# Line_Sensor.net
KiCad netlist of a schematic drawn in EAGLE
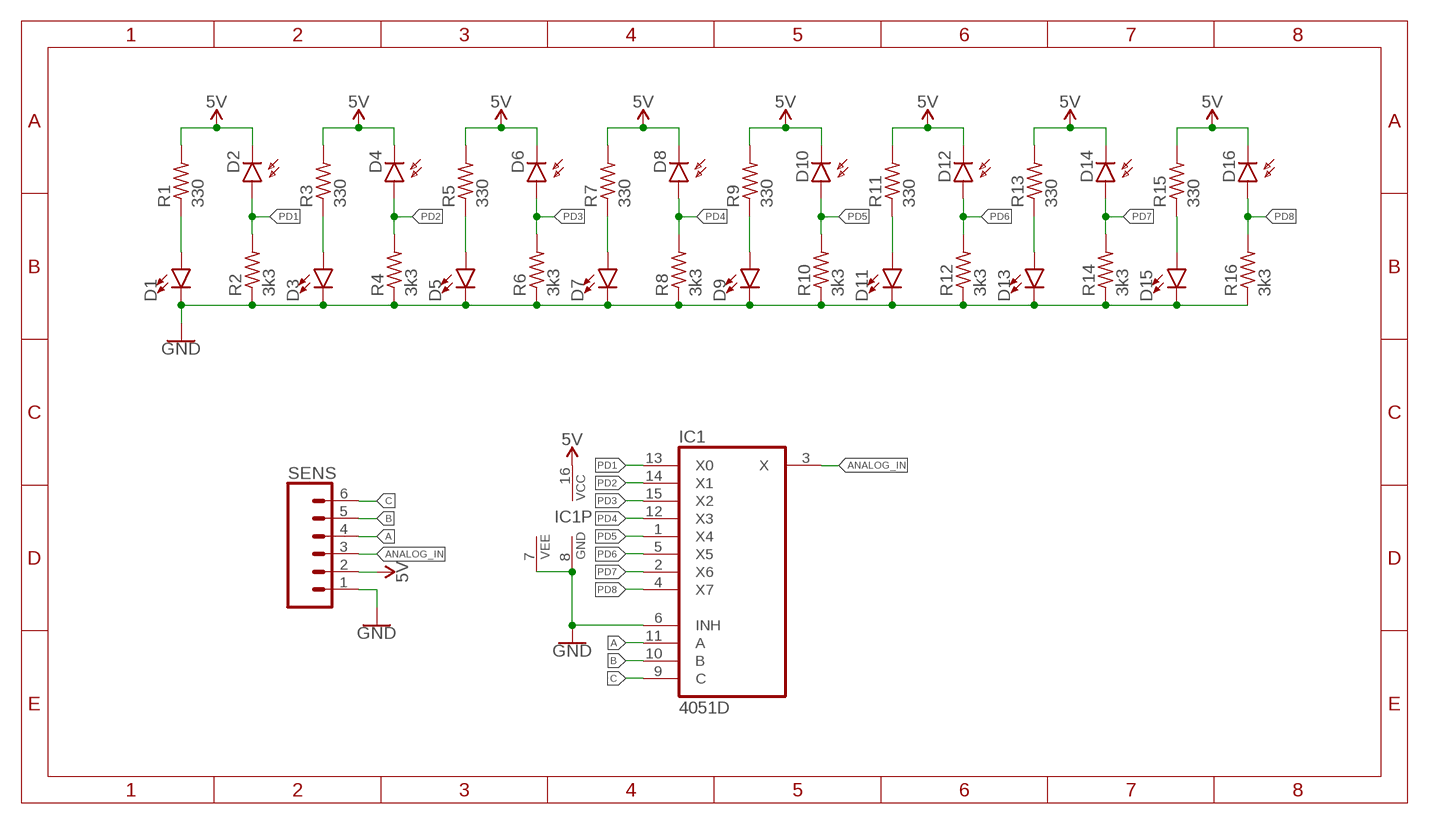
[diagram p0: schematic, sheet 1]

(export (version "E")
  (design (tool "Eeschema 10.0.6"))
  (components
    (comp (ref "D1")
      (value "LED3MM")
      (footprint "eagle-import:LED_3MM")
      (libsource (lib "eagle-import") (part "LED3MM"))
    )
    (comp (ref "D2")
      (value "SFH225")
      (footprint "eagle-import:SFH225")
      (libsource (lib "eagle-import") (part "SFH225"))
    )
    (comp (ref "D3")
      (value "LED3MM")
      (footprint "eagle-import:LED_3MM")
      (libsource (lib "eagle-import") (part "LED3MM"))
    )
    (comp (ref "D4")
      (value "SFH225")
      (footprint "eagle-import:SFH225")
      (libsource (lib "eagle-import") (part "SFH225"))
    )
    (comp (ref "D5")
      (value "LED3MM")
      (footprint "eagle-import:LED_3MM")
      (libsource (lib "eagle-import") (part "LED3MM"))
    )
    (comp (ref "D6")
      (value "SFH225")
      (footprint "eagle-import:SFH225")
      (libsource (lib "eagle-import") (part "SFH225"))
    )
    (comp (ref "D7")
      (value "LED3MM")
      (footprint "eagle-import:LED_3MM")
      (libsource (lib "eagle-import") (part "LED3MM"))
    )
    (comp (ref "D8")
      (value "SFH225")
      (footprint "eagle-import:SFH225")
      (libsource (lib "eagle-import") (part "SFH225"))
    )
    (comp (ref "D9")
      (value "LED3MM")
      (footprint "eagle-import:LED_3MM")
      (libsource (lib "eagle-import") (part "LED3MM"))
    )
    (comp (ref "D10")
      (value "SFH225")
      (footprint "eagle-import:SFH225")
      (libsource (lib "eagle-import") (part "SFH225"))
    )
    (comp (ref "D11")
      (value "LED3MM")
      (footprint "eagle-import:LED_3MM")
      (libsource (lib "eagle-import") (part "LED3MM"))
    )
    (comp (ref "D12")
      (value "SFH225")
      (footprint "eagle-import:SFH225")
      (libsource (lib "eagle-import") (part "SFH225"))
    )
    (comp (ref "D13")
      (value "LED3MM")
      (footprint "eagle-import:LED_3MM")
      (libsource (lib "eagle-import") (part "LED3MM"))
    )
    (comp (ref "D14")
      (value "SFH225")
      (footprint "eagle-import:SFH225")
      (libsource (lib "eagle-import") (part "SFH225"))
    )
    (comp (ref "D15")
      (value "LED3MM")
      (footprint "eagle-import:LED_3MM")
      (libsource (lib "eagle-import") (part "LED3MM"))
    )
    (comp (ref "D16")
      (value "SFH225")
      (footprint "eagle-import:SFH225")
      (libsource (lib "eagle-import") (part "SFH225"))
    )
    (comp (ref "IC1")
      (value "4051D")
      (footprint "eagle-import:SO16")
      (libsource (lib "eagle-import") (part "4051D"))
    )
    (comp (ref "R1")
      (value "330")
      (footprint "eagle-import:0207_9")
      (libsource (lib "eagle-import") (part "R-US_0207/9"))
    )
    (comp (ref "R2")
      (value "3k3")
      (footprint "eagle-import:0207_9")
      (libsource (lib "eagle-import") (part "R-US_0207/9"))
    )
    (comp (ref "R3")
      (value "330")
      (footprint "eagle-import:0207_9")
      (libsource (lib "eagle-import") (part "R-US_0207/9"))
    )
    (comp (ref "R4")
      (value "3k3")
      (footprint "eagle-import:0207_9")
      (libsource (lib "eagle-import") (part "R-US_0207/9"))
    )
    (comp (ref "R5")
      (value "330")
      (footprint "eagle-import:0207_9")
      (libsource (lib "eagle-import") (part "R-US_0207/9"))
    )
    (comp (ref "R6")
      (value "3k3")
      (footprint "eagle-import:0207_9")
      (libsource (lib "eagle-import") (part "R-US_0207/9"))
    )
    (comp (ref "R7")
      (value "330")
      (footprint "eagle-import:0207_9")
      (libsource (lib "eagle-import") (part "R-US_0207/9"))
    )
    (comp (ref "R8")
      (value "3k3")
      (footprint "eagle-import:0207_9")
      (libsource (lib "eagle-import") (part "R-US_0207/9"))
    )
    (comp (ref "R9")
      (value "330")
      (footprint "eagle-import:0207_9")
      (libsource (lib "eagle-import") (part "R-US_0207/9"))
    )
    (comp (ref "R10")
      (value "3k3")
      (footprint "eagle-import:0207_9")
      (libsource (lib "eagle-import") (part "R-US_0207/9"))
    )
    (comp (ref "R11")
      (value "330")
      (footprint "eagle-import:0207_9")
      (libsource (lib "eagle-import") (part "R-US_0207/9"))
    )
    (comp (ref "R12")
      (value "3k3")
      (footprint "eagle-import:0207_9")
      (libsource (lib "eagle-import") (part "R-US_0207/9"))
    )
    (comp (ref "R13")
      (value "330")
      (footprint "eagle-import:0207_9")
      (libsource (lib "eagle-import") (part "R-US_0207/9"))
    )
    (comp (ref "R14")
      (value "3k3")
      (footprint "eagle-import:0207_9")
      (libsource (lib "eagle-import") (part "R-US_0207/9"))
    )
    (comp (ref "R15")
      (value "330")
      (footprint "eagle-import:0207_9")
      (libsource (lib "eagle-import") (part "R-US_0207/9"))
    )
    (comp (ref "R16")
      (value "3k3")
      (footprint "eagle-import:0207_9")
      (libsource (lib "eagle-import") (part "R-US_0207/9"))
    )
    (comp (ref "SENS")
      (value "CONN_06SILK_FEMALE_PTH")
      (footprint "eagle-import:1X06")
      (libsource (lib "eagle-import") (part "CONN_06SILK_FEMALE_PTH"))
    )
  )
  (nets
    (net (code "1") (name "5V") (class "Default")
      (node (ref "D10") (pin "K") (pinfunction "C_K") (pintype "passive"))
      (node (ref "D12") (pin "K") (pinfunction "C_K") (pintype "passive"))
      (node (ref "D14") (pin "K") (pinfunction "C_K") (pintype "passive"))
      (node (ref "D16") (pin "K") (pinfunction "C_K") (pintype "passive"))
      (node (ref "D2") (pin "K") (pinfunction "C_K") (pintype "passive"))
      (node (ref "D4") (pin "K") (pinfunction "C_K") (pintype "passive"))
      (node (ref "D6") (pin "K") (pinfunction "C_K") (pintype "passive"))
      (node (ref "D8") (pin "K") (pinfunction "C_K") (pintype "passive"))
      (node (ref "IC1") (pin "16") (pinfunction "VCC_16") (pintype "power_in"))
      (node (ref "R1") (pin "2") (pinfunction "2_2") (pintype "passive"))
      (node (ref "R11") (pin "2") (pinfunction "2_2") (pintype "passive"))
      (node (ref "R13") (pin "2") (pinfunction "2_2") (pintype "passive"))
      (node (ref "R15") (pin "2") (pinfunction "2_2") (pintype "passive"))
      (node (ref "R3") (pin "2") (pinfunction "2_2") (pintype "passive"))
      (node (ref "R5") (pin "2") (pinfunction "2_2") (pintype "passive"))
      (node (ref "R7") (pin "2") (pinfunction "2_2") (pintype "passive"))
      (node (ref "R9") (pin "2") (pinfunction "2_2") (pintype "passive"))
      (node (ref "SENS") (pin "2") (pinfunction "2_2") (pintype "passive"))
    )
    (net (code "2") (name "A") (class "Default")
      (node (ref "IC1") (pin "11") (pinfunction "A_11") (pintype "input"))
      (node (ref "SENS") (pin "4") (pinfunction "4_4") (pintype "passive"))
    )
    (net (code "3") (name "ANALOG_IN") (class "Default")
      (node (ref "IC1") (pin "3") (pinfunction "X_3") (pintype "bidirectional"))
      (node (ref "SENS") (pin "3") (pinfunction "3_3") (pintype "passive"))
    )
    (net (code "4") (name "B") (class "Default")
      (node (ref "IC1") (pin "10") (pinfunction "B_10") (pintype "input"))
      (node (ref "SENS") (pin "5") (pinfunction "5_5") (pintype "passive"))
    )
    (net (code "5") (name "C") (class "Default")
      (node (ref "IC1") (pin "9") (pinfunction "C_9") (pintype "input"))
      (node (ref "SENS") (pin "6") (pinfunction "6_6") (pintype "passive"))
    )
    (net (code "6") (name "GND") (class "Default")
      (node (ref "D1") (pin "K") (pinfunction "C_K") (pintype "passive"))
      (node (ref "D11") (pin "K") (pinfunction "C_K") (pintype "passive"))
      (node (ref "D13") (pin "K") (pinfunction "C_K") (pintype "passive"))
      (node (ref "D15") (pin "K") (pinfunction "C_K") (pintype "passive"))
      (node (ref "D3") (pin "K") (pinfunction "C_K") (pintype "passive"))
      (node (ref "D5") (pin "K") (pinfunction "C_K") (pintype "passive"))
      (node (ref "D7") (pin "K") (pinfunction "C_K") (pintype "passive"))
      (node (ref "D9") (pin "K") (pinfunction "C_K") (pintype "passive"))
      (node (ref "IC1") (pin "6") (pinfunction "INH_6") (pintype "input"))
      (node (ref "IC1") (pin "7") (pinfunction "VEE_7") (pintype "power_in"))
      (node (ref "IC1") (pin "8") (pinfunction "GND_8") (pintype "power_in"))
      (node (ref "R10") (pin "1") (pinfunction "1_1") (pintype "passive"))
      (node (ref "R12") (pin "1") (pinfunction "1_1") (pintype "passive"))
      (node (ref "R14") (pin "1") (pinfunction "1_1") (pintype "passive"))
      (node (ref "R16") (pin "1") (pinfunction "1_1") (pintype "passive"))
      (node (ref "R2") (pin "1") (pinfunction "1_1") (pintype "passive"))
      (node (ref "R4") (pin "1") (pinfunction "1_1") (pintype "passive"))
      (node (ref "R6") (pin "1") (pinfunction "1_1") (pintype "passive"))
      (node (ref "R8") (pin "1") (pinfunction "1_1") (pintype "passive"))
      (node (ref "SENS") (pin "1") (pinfunction "1_1") (pintype "passive"))
    )
    (net (code "7") (name "Net-(D1-PadA)") (class "Default")
      (node (ref "D1") (pin "A") (pinfunction "A_A") (pintype "passive"))
      (node (ref "R1") (pin "1") (pinfunction "1_1") (pintype "passive"))
    )
    (net (code "8") (name "Net-(D3-PadA)") (class "Default")
      (node (ref "D3") (pin "A") (pinfunction "A_A") (pintype "passive"))
      (node (ref "R3") (pin "1") (pinfunction "1_1") (pintype "passive"))
    )
    (net (code "9") (name "Net-(D5-PadA)") (class "Default")
      (node (ref "D5") (pin "A") (pinfunction "A_A") (pintype "passive"))
      (node (ref "R5") (pin "1") (pinfunction "1_1") (pintype "passive"))
    )
    (net (code "10") (name "Net-(D7-PadA)") (class "Default")
      (node (ref "D7") (pin "A") (pinfunction "A_A") (pintype "passive"))
      (node (ref "R7") (pin "1") (pinfunction "1_1") (pintype "passive"))
    )
    (net (code "11") (name "Net-(D9-PadA)") (class "Default")
      (node (ref "D9") (pin "A") (pinfunction "A_A") (pintype "passive"))
      (node (ref "R9") (pin "1") (pinfunction "1_1") (pintype "passive"))
    )
    (net (code "12") (name "Net-(D11-PadA)") (class "Default")
      (node (ref "D11") (pin "A") (pinfunction "A_A") (pintype "passive"))
      (node (ref "R11") (pin "1") (pinfunction "1_1") (pintype "passive"))
    )
    (net (code "13") (name "Net-(D13-PadA)") (class "Default")
      (node (ref "D13") (pin "A") (pinfunction "A_A") (pintype "passive"))
      (node (ref "R13") (pin "1") (pinfunction "1_1") (pintype "passive"))
    )
    (net (code "14") (name "Net-(D15-PadA)") (class "Default")
      (node (ref "D15") (pin "A") (pinfunction "A_A") (pintype "passive"))
      (node (ref "R15") (pin "1") (pinfunction "1_1") (pintype "passive"))
    )
    (net (code "15") (name "PD1") (class "Default")
      (node (ref "D2") (pin "A") (pinfunction "A_A") (pintype "passive"))
      (node (ref "IC1") (pin "13") (pinfunction "X0_13") (pintype "bidirectional"))
      (node (ref "R2") (pin "2") (pinfunction "2_2") (pintype "passive"))
    )
    (net (code "16") (name "PD2") (class "Default")
      (node (ref "D4") (pin "A") (pinfunction "A_A") (pintype "passive"))
      (node (ref "IC1") (pin "14") (pinfunction "X1_14") (pintype "bidirectional"))
      (node (ref "R4") (pin "2") (pinfunction "2_2") (pintype "passive"))
    )
    (net (code "17") (name "PD3") (class "Default")
      (node (ref "D6") (pin "A") (pinfunction "A_A") (pintype "passive"))
      (node (ref "IC1") (pin "15") (pinfunction "X2_15") (pintype "bidirectional"))
      (node (ref "R6") (pin "2") (pinfunction "2_2") (pintype "passive"))
    )
    (net (code "18") (name "PD4") (class "Default")
      (node (ref "D8") (pin "A") (pinfunction "A_A") (pintype "passive"))
      (node (ref "IC1") (pin "12") (pinfunction "X3_12") (pintype "bidirectional"))
      (node (ref "R8") (pin "2") (pinfunction "2_2") (pintype "passive"))
    )
    (net (code "19") (name "PD5") (class "Default")
      (node (ref "D10") (pin "A") (pinfunction "A_A") (pintype "passive"))
      (node (ref "IC1") (pin "1") (pinfunction "X4_1") (pintype "bidirectional"))
      (node (ref "R10") (pin "2") (pinfunction "2_2") (pintype "passive"))
    )
    (net (code "20") (name "PD6") (class "Default")
      (node (ref "D12") (pin "A") (pinfunction "A_A") (pintype "passive"))
      (node (ref "IC1") (pin "5") (pinfunction "X5_5") (pintype "bidirectional"))
      (node (ref "R12") (pin "2") (pinfunction "2_2") (pintype "passive"))
    )
    (net (code "21") (name "PD7") (class "Default")
      (node (ref "D14") (pin "A") (pinfunction "A_A") (pintype "passive"))
      (node (ref "IC1") (pin "2") (pinfunction "X6_2") (pintype "bidirectional"))
      (node (ref "R14") (pin "2") (pinfunction "2_2") (pintype "passive"))
    )
    (net (code "22") (name "PD8") (class "Default")
      (node (ref "D16") (pin "A") (pinfunction "A_A") (pintype "passive"))
      (node (ref "IC1") (pin "4") (pinfunction "X7_4") (pintype "bidirectional"))
      (node (ref "R16") (pin "2") (pinfunction "2_2") (pintype "passive"))
    )
  )
)
